# Exoskeleton_PCB_v2.net
KiCad netlist of a schematic drawn in EAGLE
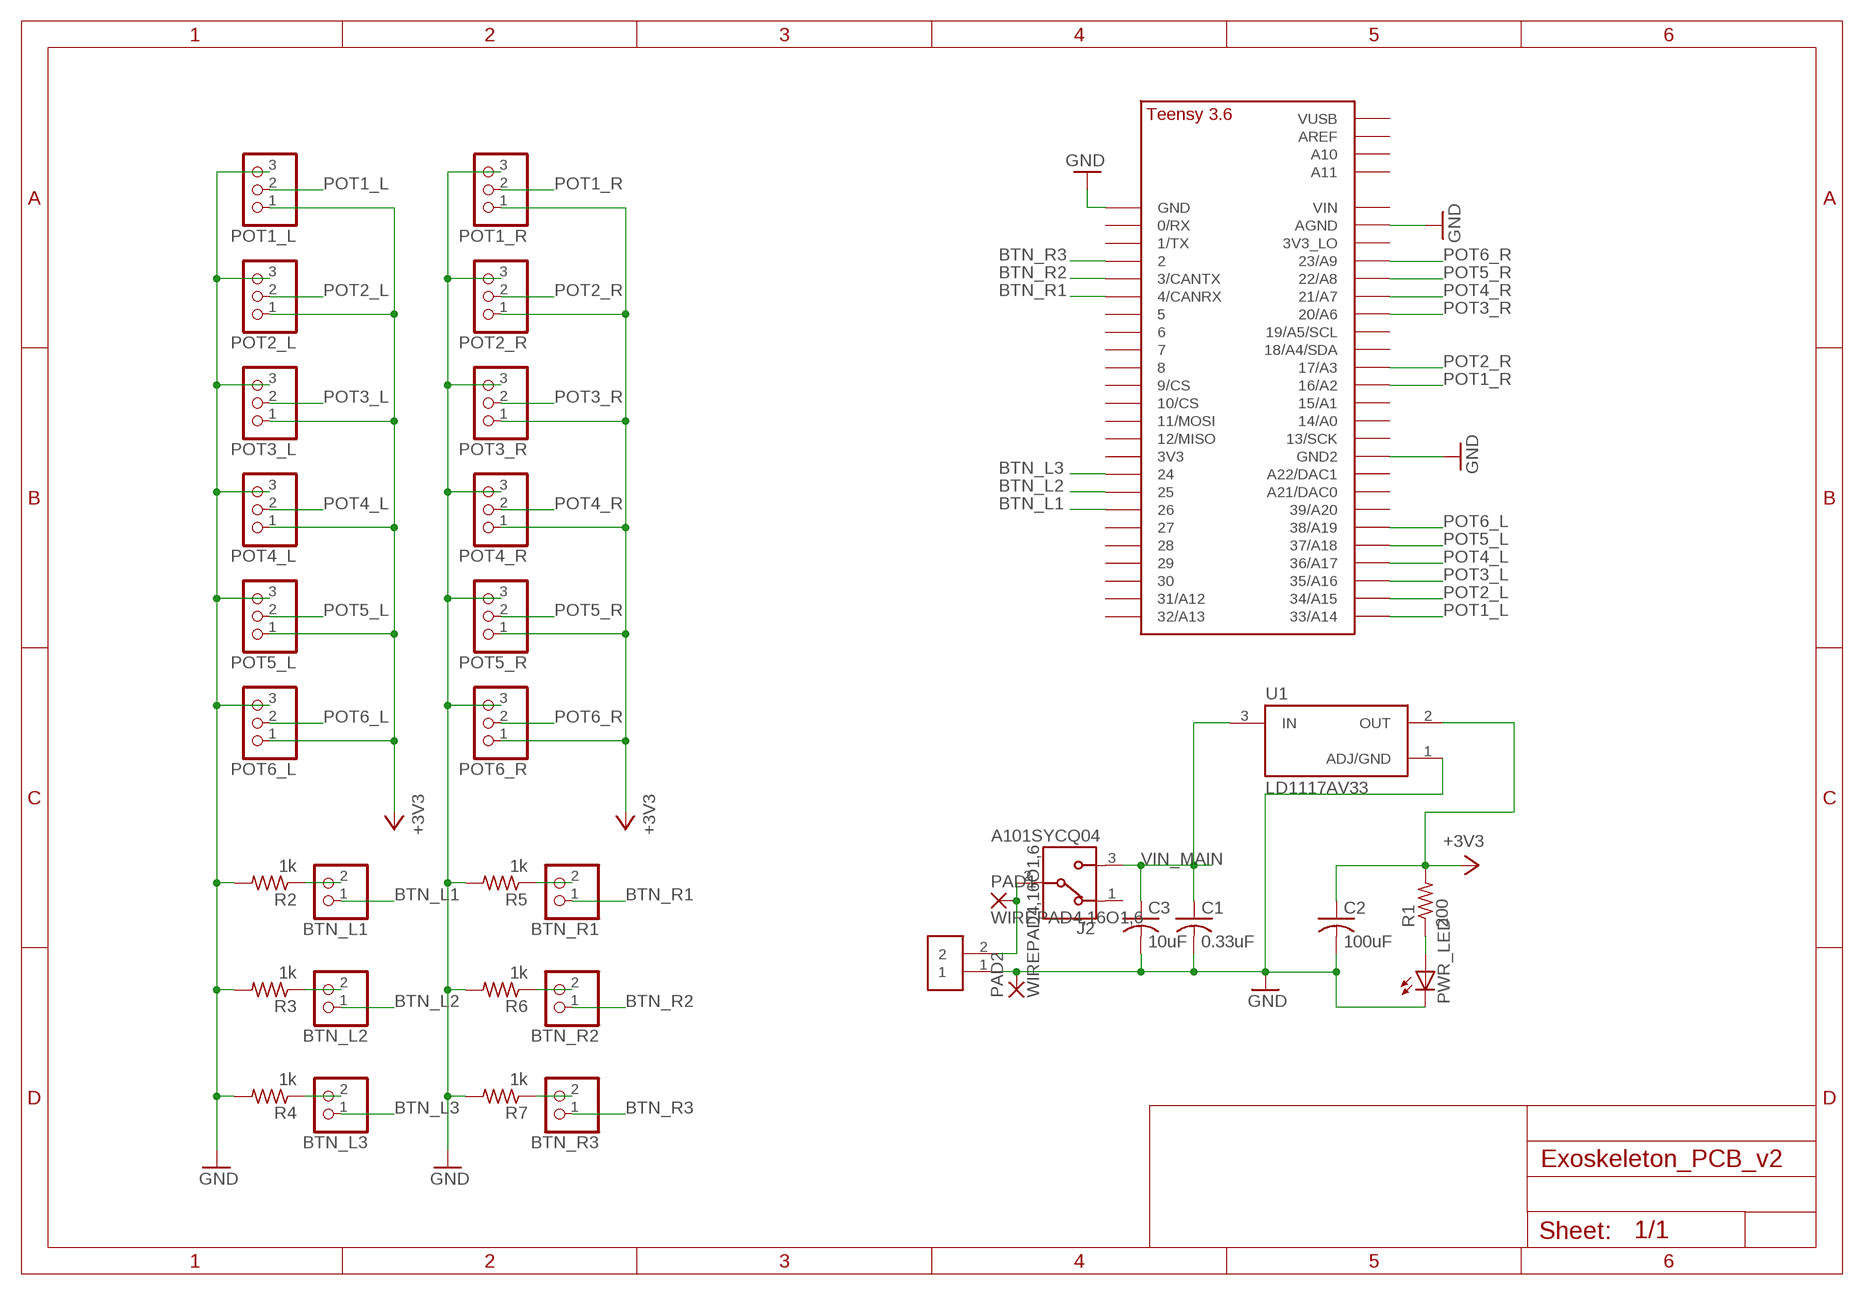
[diagram p0: schematic, sheet 1]

(export (version "E")
  (design (tool "Eeschema 10.0.6"))
  (components
    (comp (ref "BTN_L1")
      (value "PINHD-1X2")
      (footprint "eagle-import:1X02")
      (libsource (lib "eagle-import") (part "PINHD-1X2"))
    )
    (comp (ref "BTN_L2")
      (value "PINHD-1X2")
      (footprint "eagle-import:1X02")
      (libsource (lib "eagle-import") (part "PINHD-1X2"))
    )
    (comp (ref "BTN_L3")
      (value "PINHD-1X2")
      (footprint "eagle-import:1X02")
      (libsource (lib "eagle-import") (part "PINHD-1X2"))
    )
    (comp (ref "BTN_R1")
      (value "PINHD-1X2")
      (footprint "eagle-import:1X02")
      (libsource (lib "eagle-import") (part "PINHD-1X2"))
    )
    (comp (ref "BTN_R2")
      (value "PINHD-1X2")
      (footprint "eagle-import:1X02")
      (libsource (lib "eagle-import") (part "PINHD-1X2"))
    )
    (comp (ref "BTN_R3")
      (value "PINHD-1X2")
      (footprint "eagle-import:1X02")
      (libsource (lib "eagle-import") (part "PINHD-1X2"))
    )
    (comp (ref "C1")
      (value "0.33uF")
      (footprint "eagle-import:C050-030X075")
      (libsource (lib "eagle-import") (part "C-US050-030X075"))
    )
    (comp (ref "C2")
      (value "100uF")
      (footprint "eagle-import:C050-030X075")
      (libsource (lib "eagle-import") (part "C-US050-030X075"))
    )
    (comp (ref "C3")
      (value "10uF")
      (footprint "eagle-import:C050-030X075")
      (libsource (lib "eagle-import") (part "C-US050-030X075"))
    )
    (comp (ref "J1")
      (value "282837-2")
      (footprint "eagle-import:TE_282837-2")
      (fields (field (name "MF") "TE Connectivity"))
      (libsource (lib "eagle-import") (part "282837-2"))
    )
    (comp (ref "J2")
      (value "A101SYCQ04")
      (footprint "eagle-import:TE_A101SYCQ04")
      (fields (field (name "COMMENT") "4-1825136-5") (field (name "MF") "TE Connectivity"))
      (libsource (lib "eagle-import") (part "A101SYCQ04"))
    )
    (comp (ref "PAD1")
      (value "WIREPAD4,16O1,6")
      (footprint "eagle-import:4,16O1,6")
      (libsource (lib "eagle-import") (part "WIREPAD4,16O1,6"))
    )
    (comp (ref "PAD2")
      (value "WIREPAD4,16O1,6")
      (footprint "eagle-import:4,16O1,6")
      (libsource (lib "eagle-import") (part "WIREPAD4,16O1,6"))
    )
    (comp (ref "POT1_L")
      (value "PINHD-1X3")
      (footprint "eagle-import:1X03")
      (libsource (lib "eagle-import") (part "PINHD-1X3"))
    )
    (comp (ref "POT1_R")
      (value "PINHD-1X3")
      (footprint "eagle-import:1X03")
      (libsource (lib "eagle-import") (part "PINHD-1X3"))
    )
    (comp (ref "POT2_L")
      (value "PINHD-1X3")
      (footprint "eagle-import:1X03")
      (libsource (lib "eagle-import") (part "PINHD-1X3"))
    )
    (comp (ref "POT2_R")
      (value "PINHD-1X3")
      (footprint "eagle-import:1X03")
      (libsource (lib "eagle-import") (part "PINHD-1X3"))
    )
    (comp (ref "POT3_L")
      (value "PINHD-1X3")
      (footprint "eagle-import:1X03")
      (libsource (lib "eagle-import") (part "PINHD-1X3"))
    )
    (comp (ref "POT3_R")
      (value "PINHD-1X3")
      (footprint "eagle-import:1X03")
      (libsource (lib "eagle-import") (part "PINHD-1X3"))
    )
    (comp (ref "POT4_L")
      (value "PINHD-1X3")
      (footprint "eagle-import:1X03")
      (libsource (lib "eagle-import") (part "PINHD-1X3"))
    )
    (comp (ref "POT4_R")
      (value "PINHD-1X3")
      (footprint "eagle-import:1X03")
      (libsource (lib "eagle-import") (part "PINHD-1X3"))
    )
    (comp (ref "POT5_L")
      (value "PINHD-1X3")
      (footprint "eagle-import:1X03")
      (libsource (lib "eagle-import") (part "PINHD-1X3"))
    )
    (comp (ref "POT5_R")
      (value "PINHD-1X3")
      (footprint "eagle-import:1X03")
      (libsource (lib "eagle-import") (part "PINHD-1X3"))
    )
    (comp (ref "POT6_L")
      (value "PINHD-1X3")
      (footprint "eagle-import:1X03")
      (libsource (lib "eagle-import") (part "PINHD-1X3"))
    )
    (comp (ref "POT6_R")
      (value "PINHD-1X3")
      (footprint "eagle-import:1X03")
      (libsource (lib "eagle-import") (part "PINHD-1X3"))
    )
    (comp (ref "PWR_LED")
      (value "LED5MM")
      (footprint "eagle-import:LED5MM")
      (libsource (lib "eagle-import") (part "LED5MM"))
    )
    (comp (ref "R1")
      (value "200")
      (footprint "eagle-import:0207_9")
      (libsource (lib "eagle-import") (part "R-US_0207/9"))
    )
    (comp (ref "R2")
      (value "1k")
      (footprint "eagle-import:0207_9")
      (libsource (lib "eagle-import") (part "R-US_0207/9"))
    )
    (comp (ref "R3")
      (value "1k")
      (footprint "eagle-import:0207_9")
      (libsource (lib "eagle-import") (part "R-US_0207/9"))
    )
    (comp (ref "R4")
      (value "1k")
      (footprint "eagle-import:0207_9")
      (libsource (lib "eagle-import") (part "R-US_0207/9"))
    )
    (comp (ref "R5")
      (value "1k")
      (footprint "eagle-import:0207_9")
      (libsource (lib "eagle-import") (part "R-US_0207/9"))
    )
    (comp (ref "R6")
      (value "1k")
      (footprint "eagle-import:0207_9")
      (libsource (lib "eagle-import") (part "R-US_0207/9"))
    )
    (comp (ref "R7")
      (value "1k")
      (footprint "eagle-import:0207_9")
      (libsource (lib "eagle-import") (part "R-US_0207/9"))
    )
    (comp (ref "U$1")
      (value "TEENSY_3.5/3.6_BASIC")
      (footprint "eagle-import:TEENSY_3.5_3.6_BASIC")
      (libsource (lib "eagle-import") (part "TEENSY_3.5/3.6_BASIC"))
    )
    (comp (ref "U1")
      (value "LD1117AV33")
      (footprint "eagle-import:TO255P1020X450X1968-3")
      (fields (field (name "MF") "STMicroelectronics"))
      (libsource (lib "eagle-import") (part "LD1117AV33"))
    )
  )
  (nets
    (net (code "1") (name "+3V3") (class "Default")
      (node (ref "C2") (pin "1") (pinfunction "1_1") (pintype "passive"))
      (node (ref "POT1_L") (pin "1") (pinfunction "1_1") (pintype "passive"))
      (node (ref "POT1_R") (pin "1") (pinfunction "1_1") (pintype "passive"))
      (node (ref "POT2_L") (pin "1") (pinfunction "1_1") (pintype "passive"))
      (node (ref "POT2_R") (pin "1") (pinfunction "1_1") (pintype "passive"))
      (node (ref "POT3_L") (pin "1") (pinfunction "1_1") (pintype "passive"))
      (node (ref "POT3_R") (pin "1") (pinfunction "1_1") (pintype "passive"))
      (node (ref "POT4_L") (pin "1") (pinfunction "1_1") (pintype "passive"))
      (node (ref "POT4_R") (pin "1") (pinfunction "1_1") (pintype "passive"))
      (node (ref "POT5_L") (pin "1") (pinfunction "1_1") (pintype "passive"))
      (node (ref "POT5_R") (pin "1") (pinfunction "1_1") (pintype "passive"))
      (node (ref "POT6_L") (pin "1") (pinfunction "1_1") (pintype "passive"))
      (node (ref "POT6_R") (pin "1") (pinfunction "1_1") (pintype "passive"))
      (node (ref "R1") (pin "2") (pinfunction "2_2") (pintype "passive"))
      (node (ref "U1") (pin "2") (pinfunction "OUT_2") (pintype "output"))
    )
    (net (code "2") (name "/BTN_L1") (class "Default")
      (node (ref "BTN_L1") (pin "1") (pinfunction "1_1") (pintype "passive"))
      (node (ref "U$1") (pin "26") (pinfunction "26_26") (pintype "bidirectional"))
    )
    (net (code "3") (name "/BTN_L2") (class "Default")
      (node (ref "BTN_L2") (pin "1") (pinfunction "1_1") (pintype "passive"))
      (node (ref "U$1") (pin "25") (pinfunction "25_25") (pintype "bidirectional"))
    )
    (net (code "4") (name "/BTN_L3") (class "Default")
      (node (ref "BTN_L3") (pin "1") (pinfunction "1_1") (pintype "passive"))
      (node (ref "U$1") (pin "24") (pinfunction "24_24") (pintype "bidirectional"))
    )
    (net (code "5") (name "/BTN_R1") (class "Default")
      (node (ref "BTN_R1") (pin "1") (pinfunction "1_1") (pintype "passive"))
      (node (ref "U$1") (pin "4/CANRX") (pinfunction "4/CANRX_4/CANRX") (pintype "bidirectional"))
    )
    (net (code "6") (name "/BTN_R2") (class "Default")
      (node (ref "BTN_R2") (pin "1") (pinfunction "1_1") (pintype "passive"))
      (node (ref "U$1") (pin "3/CANTX") (pinfunction "3/CANTX_3/CANTX") (pintype "bidirectional"))
    )
    (net (code "7") (name "/BTN_R3") (class "Default")
      (node (ref "BTN_R3") (pin "1") (pinfunction "1_1") (pintype "passive"))
      (node (ref "U$1") (pin "2") (pinfunction "2_2") (pintype "bidirectional"))
    )
    (net (code "8") (name "/POT1_L") (class "Default")
      (node (ref "POT1_L") (pin "2") (pinfunction "2_2") (pintype "passive"))
      (node (ref "U$1") (pin "33/A14") (pinfunction "33/A14_33/A14") (pintype "bidirectional"))
    )
    (net (code "9") (name "/POT1_R") (class "Default")
      (node (ref "POT1_R") (pin "2") (pinfunction "2_2") (pintype "passive"))
      (node (ref "U$1") (pin "16/A2") (pinfunction "16/A2_16/A2") (pintype "bidirectional"))
    )
    (net (code "10") (name "/POT2_L") (class "Default")
      (node (ref "POT2_L") (pin "2") (pinfunction "2_2") (pintype "passive"))
      (node (ref "U$1") (pin "34/A15") (pinfunction "34/A15_34/A15") (pintype "bidirectional"))
    )
    (net (code "11") (name "/POT2_R") (class "Default")
      (node (ref "POT2_R") (pin "2") (pinfunction "2_2") (pintype "passive"))
      (node (ref "U$1") (pin "17/A3") (pinfunction "17/A3_17/A3") (pintype "bidirectional"))
    )
    (net (code "12") (name "/POT3_L") (class "Default")
      (node (ref "POT3_L") (pin "2") (pinfunction "2_2") (pintype "passive"))
      (node (ref "U$1") (pin "35/A16") (pinfunction "35/A16_35/A16") (pintype "bidirectional"))
    )
    (net (code "13") (name "/POT3_R") (class "Default")
      (node (ref "POT3_R") (pin "2") (pinfunction "2_2") (pintype "passive"))
      (node (ref "U$1") (pin "20/A6") (pinfunction "20/A6_20/A6") (pintype "bidirectional"))
    )
    (net (code "14") (name "/POT4_L") (class "Default")
      (node (ref "POT4_L") (pin "2") (pinfunction "2_2") (pintype "passive"))
      (node (ref "U$1") (pin "36/A17") (pinfunction "36/A17_36/A17") (pintype "bidirectional"))
    )
    (net (code "15") (name "/POT4_R") (class "Default")
      (node (ref "POT4_R") (pin "2") (pinfunction "2_2") (pintype "passive"))
      (node (ref "U$1") (pin "21/A7") (pinfunction "21/A7_21/A7") (pintype "bidirectional"))
    )
    (net (code "16") (name "/POT5_L") (class "Default")
      (node (ref "POT5_L") (pin "2") (pinfunction "2_2") (pintype "passive"))
      (node (ref "U$1") (pin "37/A18") (pinfunction "37/A18_37/A18") (pintype "bidirectional"))
    )
    (net (code "17") (name "/POT5_R") (class "Default")
      (node (ref "POT5_R") (pin "2") (pinfunction "2_2") (pintype "passive"))
      (node (ref "U$1") (pin "22/A8") (pinfunction "22/A8_22/A8") (pintype "bidirectional"))
    )
    (net (code "18") (name "/POT6_L") (class "Default")
      (node (ref "POT6_L") (pin "2") (pinfunction "2_2") (pintype "passive"))
      (node (ref "U$1") (pin "38/A19") (pinfunction "38/A19_38/A19") (pintype "bidirectional"))
    )
    (net (code "19") (name "/POT6_R") (class "Default")
      (node (ref "POT6_R") (pin "2") (pinfunction "2_2") (pintype "passive"))
      (node (ref "U$1") (pin "23/A9") (pinfunction "23/A9_23/A9") (pintype "bidirectional"))
    )
    (net (code "20") (name "/VIN_MAIN") (class "Default")
      (node (ref "C1") (pin "1") (pinfunction "1_1") (pintype "passive"))
      (node (ref "C3") (pin "1") (pinfunction "1_1") (pintype "passive"))
      (node (ref "J2") (pin "3") (pinfunction "3_3") (pintype "passive"))
      (node (ref "U1") (pin "3") (pinfunction "IN_3") (pintype "input"))
    )
    (net (code "21") (name "GND") (class "Default")
      (node (ref "C1") (pin "2") (pinfunction "2_2") (pintype "passive"))
      (node (ref "C2") (pin "2") (pinfunction "2_2") (pintype "passive"))
      (node (ref "C3") (pin "2") (pinfunction "2_2") (pintype "passive"))
      (node (ref "J1") (pin "1") (pinfunction "1_1") (pintype "passive"))
      (node (ref "PAD2") (pin "1") (pinfunction "P_1") (pintype "passive"))
      (node (ref "POT1_L") (pin "3") (pinfunction "3_3") (pintype "passive"))
      (node (ref "POT1_R") (pin "3") (pinfunction "3_3") (pintype "passive"))
      (node (ref "POT2_L") (pin "3") (pinfunction "3_3") (pintype "passive"))
      (node (ref "POT2_R") (pin "3") (pinfunction "3_3") (pintype "passive"))
      (node (ref "POT3_L") (pin "3") (pinfunction "3_3") (pintype "passive"))
      (node (ref "POT3_R") (pin "3") (pinfunction "3_3") (pintype "passive"))
      (node (ref "POT4_L") (pin "3") (pinfunction "3_3") (pintype "passive"))
      (node (ref "POT4_R") (pin "3") (pinfunction "3_3") (pintype "passive"))
      (node (ref "POT5_L") (pin "3") (pinfunction "3_3") (pintype "passive"))
      (node (ref "POT5_R") (pin "3") (pinfunction "3_3") (pintype "passive"))
      (node (ref "POT6_L") (pin "3") (pinfunction "3_3") (pintype "passive"))
      (node (ref "POT6_R") (pin "3") (pinfunction "3_3") (pintype "passive"))
      (node (ref "PWR_LED") (pin "K") (pinfunction "C_K") (pintype "passive"))
      (node (ref "R2") (pin "2") (pinfunction "2_2") (pintype "passive"))
      (node (ref "R3") (pin "2") (pinfunction "2_2") (pintype "passive"))
      (node (ref "R4") (pin "2") (pinfunction "2_2") (pintype "passive"))
      (node (ref "R5") (pin "2") (pinfunction "2_2") (pintype "passive"))
      (node (ref "R6") (pin "2") (pinfunction "2_2") (pintype "passive"))
      (node (ref "R7") (pin "2") (pinfunction "2_2") (pintype "passive"))
      (node (ref "U$1") (pin "AGND") (pinfunction "AGND_AGND") (pintype "bidirectional"))
      (node (ref "U$1") (pin "GND") (pinfunction "GND_GND") (pintype "bidirectional"))
      (node (ref "U$1") (pin "GND2") (pinfunction "GND2_GND2") (pintype "bidirectional"))
      (node (ref "U1") (pin "1") (pinfunction "ADJ/GND_1") (pintype "passive"))
    )
    (net (code "22") (name "Net-(BTN_L1-Pad2)") (class "Default")
      (node (ref "BTN_L1") (pin "2") (pinfunction "2_2") (pintype "passive"))
      (node (ref "R2") (pin "1") (pinfunction "1_1") (pintype "passive"))
    )
    (net (code "23") (name "Net-(BTN_L2-Pad2)") (class "Default")
      (node (ref "BTN_L2") (pin "2") (pinfunction "2_2") (pintype "passive"))
      (node (ref "R3") (pin "1") (pinfunction "1_1") (pintype "passive"))
    )
    (net (code "24") (name "Net-(BTN_L3-Pad2)") (class "Default")
      (node (ref "BTN_L3") (pin "2") (pinfunction "2_2") (pintype "passive"))
      (node (ref "R4") (pin "1") (pinfunction "1_1") (pintype "passive"))
    )
    (net (code "25") (name "Net-(BTN_R1-Pad2)") (class "Default")
      (node (ref "BTN_R1") (pin "2") (pinfunction "2_2") (pintype "passive"))
      (node (ref "R5") (pin "1") (pinfunction "1_1") (pintype "passive"))
    )
    (net (code "26") (name "Net-(BTN_R2-Pad2)") (class "Default")
      (node (ref "BTN_R2") (pin "2") (pinfunction "2_2") (pintype "passive"))
      (node (ref "R6") (pin "1") (pinfunction "1_1") (pintype "passive"))
    )
    (net (code "27") (name "Net-(BTN_R3-Pad2)") (class "Default")
      (node (ref "BTN_R3") (pin "2") (pinfunction "2_2") (pintype "passive"))
      (node (ref "R7") (pin "1") (pinfunction "1_1") (pintype "passive"))
    )
    (net (code "28") (name "Net-(PAD1-P)") (class "Default")
      (node (ref "J1") (pin "2") (pinfunction "2_2") (pintype "passive"))
      (node (ref "J2") (pin "2") (pinfunction "2_2") (pintype "passive"))
      (node (ref "PAD1") (pin "1") (pinfunction "P_1") (pintype "passive"))
    )
    (net (code "29") (name "Net-(PWR_LED-PadA)") (class "Default")
      (node (ref "PWR_LED") (pin "A") (pinfunction "A_A") (pintype "passive"))
      (node (ref "R1") (pin "1") (pinfunction "1_1") (pintype "passive"))
    )
    (net (code "30") (name "unconnected-(J2-Pad1)") (class "Default")
      (node (ref "J2") (pin "1") (pinfunction "1_1") (pintype "passive"))
    )
    (net (code "31") (name "unconnected-(U$1-A21{slash}DAC0-Pad21{slash}DAC0)") (class "Default")
      (node (ref "U$1") (pin "21/DAC0") (pinfunction "A21/DAC0_21/DAC0") (pintype "bidirectional"))
    )
    (net (code "32") (name "unconnected-(U$1-Pad0{slash}RX)") (class "Default")
      (node (ref "U$1") (pin "0/RX") (pinfunction "0/RX_0/RX") (pintype "bidirectional"))
    )
    (net (code "33") (name "unconnected-(U$1-Pad1{slash}TX)") (class "Default")
      (node (ref "U$1") (pin "1/TX") (pinfunction "1/TX_1/TX") (pintype "bidirectional"))
    )
    (net (code "34") (name "unconnected-(U$1-Pad3V3)") (class "Default")
      (node (ref "U$1") (pin "3V3") (pinfunction "3V3_3V3") (pintype "bidirectional"))
    )
    (net (code "35") (name "unconnected-(U$1-Pad3V3_LO)") (class "Default")
      (node (ref "U$1") (pin "3V3_LO") (pinfunction "3V3_LO_3V3_LO") (pintype "bidirectional"))
    )
    (net (code "36") (name "unconnected-(U$1-Pad5)") (class "Default")
      (node (ref "U$1") (pin "5") (pinfunction "5_5") (pintype "bidirectional"))
    )
    (net (code "37") (name "unconnected-(U$1-Pad6)") (class "Default")
      (node (ref "U$1") (pin "6") (pinfunction "6_6") (pintype "bidirectional"))
    )
    (net (code "38") (name "unconnected-(U$1-Pad7)") (class "Default")
      (node (ref "U$1") (pin "7") (pinfunction "7_7") (pintype "bidirectional"))
    )
    (net (code "39") (name "unconnected-(U$1-Pad8)") (class "Default")
      (node (ref "U$1") (pin "8") (pinfunction "8_8") (pintype "bidirectional"))
    )
    (net (code "40") (name "unconnected-(U$1-Pad9{slash}CS)") (class "Default")
      (node (ref "U$1") (pin "9/CS") (pinfunction "9/CS_9/CS") (pintype "bidirectional"))
    )
    (net (code "41") (name "unconnected-(U$1-Pad10{slash}CS)") (class "Default")
      (node (ref "U$1") (pin "10/CS") (pinfunction "10/CS_10/CS") (pintype "bidirectional"))
    )
    (net (code "42") (name "unconnected-(U$1-Pad11{slash}MOSI)") (class "Default")
      (node (ref "U$1") (pin "11/MOSI") (pinfunction "11/MOSI_11/MOSI") (pintype "bidirectional"))
    )
    (net (code "43") (name "unconnected-(U$1-Pad12{slash}MISO)") (class "Default")
      (node (ref "U$1") (pin "12/MISO") (pinfunction "12/MISO_12/MISO") (pintype "bidirectional"))
    )
    (net (code "44") (name "unconnected-(U$1-Pad13{slash}SCK)") (class "Default")
      (node (ref "U$1") (pin "13/SCK") (pinfunction "13/SCK_13/SCK") (pintype "bidirectional"))
    )
    (net (code "45") (name "unconnected-(U$1-Pad14{slash}A0)") (class "Default")
      (node (ref "U$1") (pin "14/A0") (pinfunction "14/A0_14/A0") (pintype "bidirectional"))
    )
    (net (code "46") (name "unconnected-(U$1-Pad15{slash}A1)") (class "Default")
      (node (ref "U$1") (pin "15/A1") (pinfunction "15/A1_15/A1") (pintype "bidirectional"))
    )
    (net (code "47") (name "unconnected-(U$1-Pad18{slash}A4{slash}SDA)") (class "Default")
      (node (ref "U$1") (pin "18/A4/SDA") (pinfunction "18/A4/SDA_18/A4/SDA") (pintype "bidirectional"))
    )
    (net (code "48") (name "unconnected-(U$1-Pad19{slash}A5{slash}SCL)") (class "Default")
      (node (ref "U$1") (pin "19/A5/SCL") (pinfunction "19/A5/SCL_19/A5/SCL") (pintype "bidirectional"))
    )
    (net (code "49") (name "unconnected-(U$1-Pad27)") (class "Default")
      (node (ref "U$1") (pin "27") (pinfunction "27_27") (pintype "bidirectional"))
    )
    (net (code "50") (name "unconnected-(U$1-Pad28)") (class "Default")
      (node (ref "U$1") (pin "28") (pinfunction "28_28") (pintype "bidirectional"))
    )
    (net (code "51") (name "unconnected-(U$1-Pad29)") (class "Default")
      (node (ref "U$1") (pin "29") (pinfunction "29_29") (pintype "bidirectional"))
    )
    (net (code "52") (name "unconnected-(U$1-Pad30)") (class "Default")
      (node (ref "U$1") (pin "30") (pinfunction "30_30") (pintype "bidirectional"))
    )
    (net (code "53") (name "unconnected-(U$1-Pad31{slash}A12)") (class "Default")
      (node (ref "U$1") (pin "31/A12") (pinfunction "31/A12_31/A12") (pintype "bidirectional"))
    )
    (net (code "54") (name "unconnected-(U$1-Pad32{slash}A13)") (class "Default")
      (node (ref "U$1") (pin "32/A13") (pinfunction "32/A13_32/A13") (pintype "bidirectional"))
    )
    (net (code "55") (name "unconnected-(U$1-Pad39{slash}A20)") (class "Default")
      (node (ref "U$1") (pin "39/A20") (pinfunction "39/A20_39/A20") (pintype "bidirectional"))
    )
    (net (code "56") (name "unconnected-(U$1-PadA10)") (class "Default")
      (node (ref "U$1") (pin "A10") (pinfunction "A10_A10") (pintype "bidirectional"))
    )
    (net (code "57") (name "unconnected-(U$1-PadA11)") (class "Default")
      (node (ref "U$1") (pin "A11") (pinfunction "A11_A11") (pintype "bidirectional"))
    )
    (net (code "58") (name "unconnected-(U$1-PadA22{slash}DAC1)") (class "Default")
      (node (ref "U$1") (pin "A22/DAC1") (pinfunction "A22/DAC1_A22/DAC1") (pintype "bidirectional"))
    )
    (net (code "59") (name "unconnected-(U$1-PadAREF)") (class "Default")
      (node (ref "U$1") (pin "AREF") (pinfunction "AREF_AREF") (pintype "bidirectional"))
    )
    (net (code "60") (name "unconnected-(U$1-PadVIN)") (class "Default")
      (node (ref "U$1") (pin "VIN") (pinfunction "VIN_VIN") (pintype "bidirectional"))
    )
    (net (code "61") (name "unconnected-(U$1-PadVUSB)") (class "Default")
      (node (ref "U$1") (pin "VUSB") (pinfunction "VUSB_VUSB") (pintype "bidirectional"))
    )
  )
)
